# Photocoupler12Vinput.net
KiCad netlist of a schematic drawn in Altium Designer
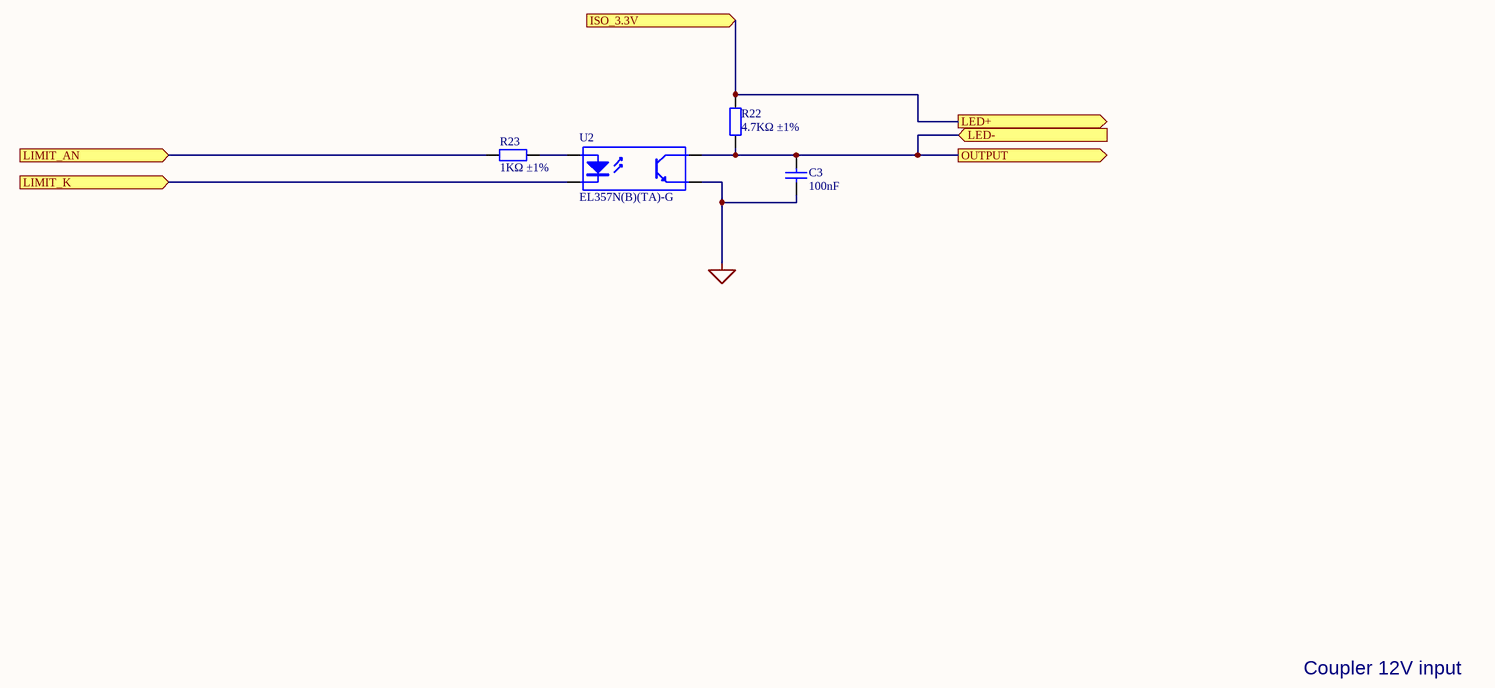
[diagram p0: Photocoupler12Vinput.SchDoc]

(export (version "E")
  (design (tool "Eeschema 10.0.6"))
  (components
    (comp (ref "C3")
      (value "100nF")
      (footprint "0402_C")
      (description "16V 100nF X7R ±10% 0402 Multilayer Ceramic Capacitors MLCC - SMD/SMT ROHS")
      (fields (field (name "MANUFACTURER") "Samsung Electro-Mechanics") (field (name "TOLERANCE") "10%"))
      (libsource (lib "Sienci_Labs") (part "0402 100nF (104) 10% 16V"))
    )
    (comp (ref "R22")
      (value "4.7KΩ ±1%")
      (footprint "0402_R")
      (description "Chip resistor")
      (fields
        (field (name "MANUFACTURER") "Uniroyal Elec")
        (field (name "MANUFACTURER PART NUMBER") "0402WGF4701TCE")
      )
      (libsource (lib "RES") (part "0402 4.7K (4701) 1%"))
    )
    (comp (ref "R23")
      (value "1KΩ ±1%")
      (footprint "0603_R")
      (description "Chip resistor")
      (fields
        (field (name "MANUFACTURER") "Uniroyal Elec")
        (field (name "MANUFACTURER PART NUMBER") "0603WAF1001T5E")
      )
      (libsource (lib "RES") (part "0603 1K (1001) 1%"))
    )
    (comp (ref "U2")
      (value "EL357N(B)(TA)-G")
      (footprint "Miscellaneous Devices LC:SOP-4_P2.54")
      (description "80V 3750V 50mA 0.1V@1mA,20mA 1 6V 1.2V DC SOP-4-2.54mm Optocouplers - Phototransistor Output ROHS")
      (fields (field (name "MANUFACTURER") "Everlight Elec"))
      (libsource (lib "IC") (part "EL357N(B)(TA)-G_[C6649]"))
    )
  )
  (nets
    (net (code "1") (name "/ISO_3.3V") (class "Default")
      (node (ref "R22") (pin "2") (pinfunction "2_2") (pintype "passive"))
    )
    (net (code "2") (name "/LED-") (class "Default")
      (node (ref "C3") (pin "2") (pinfunction "2_2") (pintype "passive"))
      (node (ref "R22") (pin "1") (pinfunction "1_1") (pintype "passive"))
      (node (ref "U2") (pin "4") (pinfunction "C_4") (pintype "passive"))
    )
    (net (code "3") (name "/LIMIT_AN") (class "Default")
      (node (ref "R23") (pin "1") (pinfunction "1_1") (pintype "passive"))
    )
    (net (code "4") (name "/LIMIT_K") (class "Default")
      (node (ref "U2") (pin "2") (pinfunction "K_2") (pintype "passive"))
    )
    (net (code "5") (name "MCU_GND") (class "Default")
      (node (ref "C3") (pin "1") (pinfunction "1_1") (pintype "passive"))
      (node (ref "U2") (pin "3") (pinfunction "E_3") (pintype "passive"))
    )
    (net (code "6") (name "Net-(U2-A)") (class "Default")
      (node (ref "R23") (pin "2") (pinfunction "2_2") (pintype "passive"))
      (node (ref "U2") (pin "1") (pinfunction "A_1") (pintype "passive"))
    )
  )
)
